# 24V_to_5V_500mA_switching_regulator.net
KiCad netlist of a schematic drawn in EAGLE
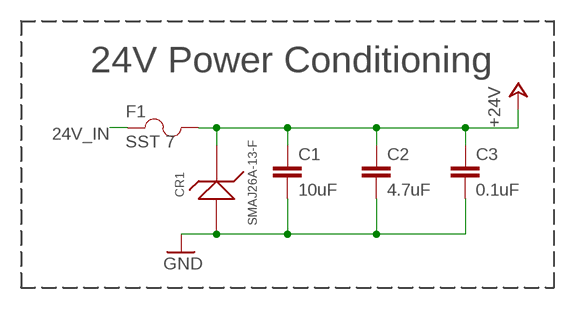
[diagram p0: schematic, sheet 1]

(export (version "E")
  (design (tool "Eeschema 10.0.6"))
  (components
    (comp (ref "C1")
      (value "10uF")
      (footprint "eagle-import:C0805")
      (libsource (lib "eagle-import") (part "10UF-GMK212BBJ106KG-T"))
    )
    (comp (ref "C2")
      (value "4.7uF")
      (footprint "eagle-import:C0805")
      (libsource (lib "eagle-import") (part "4.7UF-CL21A475KBQNNNE"))
    )
    (comp (ref "C3")
      (value "0.1uF")
      (footprint "eagle-import:C0603")
      (libsource (lib "eagle-import") (part "0.1UF-C0603C104K5RACTU"))
    )
    (comp (ref "CR1")
      (value "SMAJ26A-13-F")
      (footprint "eagle-import:SMA")
      (libsource (lib "eagle-import") (part "SMAJ26A-13-F"))
    )
    (comp (ref "F1")
      (value "SST 7")
      (footprint "eagle-import:SS")
      (libsource (lib "eagle-import") (part "SST_7"))
    )
  )
  (nets
    (net (code "1") (name "+24V") (class "Default")
      (node (ref "C1") (pin "1") (pinfunction "1_1") (pintype "passive"))
      (node (ref "C2") (pin "1") (pinfunction "1_1") (pintype "passive"))
      (node (ref "C3") (pin "1") (pinfunction "1_1") (pintype "passive"))
      (node (ref "CR1") (pin "1") (pinfunction "P$2_1") (pintype "bidirectional"))
      (node (ref "F1") (pin "2") (pinfunction "2_2") (pintype "passive"))
    )
    (net (code "2") (name "24V_IN") (class "Default")
      (node (ref "F1") (pin "1") (pinfunction "1_1") (pintype "passive"))
    )
    (net (code "3") (name "GND") (class "Default")
      (node (ref "C1") (pin "2") (pinfunction "2_2") (pintype "passive"))
      (node (ref "C2") (pin "2") (pinfunction "2_2") (pintype "passive"))
      (node (ref "C3") (pin "2") (pinfunction "2_2") (pintype "passive"))
      (node (ref "CR1") (pin "2") (pinfunction "P$1_2") (pintype "bidirectional"))
    )
  )
)
